# PAGE1.net
KiCad netlist of a schematic drawn in Altium Designer
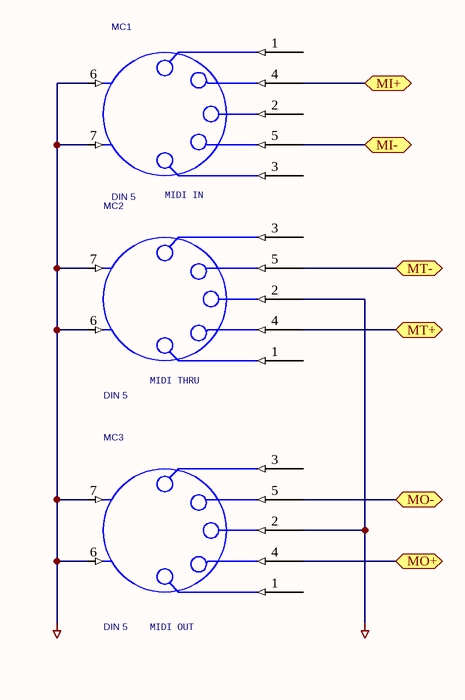
[diagram p0: PAGE1.SchDoc]

(export (version "E")
  (design (tool "Eeschema 10.0.6"))
  (components
    (comp (ref "MC1")
      (value "DIN 5")
      (fields (field (name "PART NO") "161-0505"))
      (libsource (lib "*") (part "DIN 5_0"))
    )
    (comp (ref "MC2")
      (value "DIN 5")
      (fields (field (name "PART NO") "161-0505"))
      (libsource (lib "*") (part "DIN 5_0"))
    )
    (comp (ref "MC3")
      (value "DIN 5")
      (fields (field (name "PART NO") "161-0505"))
      (libsource (lib "*") (part "DIN 5_0"))
    )
  )
  (nets
    (net (code "1") (name "/MI+") (class "Default")
      (node (ref "MC1") (pin "4") (pinfunction "4_4") (pintype "input"))
    )
    (net (code "2") (name "/MI-") (class "Default")
      (node (ref "MC1") (pin "5") (pinfunction "5_5") (pintype "input"))
    )
    (net (code "3") (name "/MO+") (class "Default")
      (node (ref "MC3") (pin "4") (pinfunction "4_4") (pintype "input"))
    )
    (net (code "4") (name "/MO-") (class "Default")
      (node (ref "MC3") (pin "5") (pinfunction "5_5") (pintype "input"))
    )
    (net (code "5") (name "/MT+") (class "Default")
      (node (ref "MC2") (pin "4") (pinfunction "4_4") (pintype "input"))
    )
    (net (code "6") (name "/MT-") (class "Default")
      (node (ref "MC2") (pin "5") (pinfunction "5_5") (pintype "input"))
    )
    (net (code "7") (name "AGND") (class "Default")
      (node (ref "MC1") (pin "6") (pinfunction "6_6") (pintype "input"))
      (node (ref "MC1") (pin "7") (pinfunction "7_7") (pintype "input"))
      (node (ref "MC2") (pin "2") (pinfunction "2_2") (pintype "input"))
      (node (ref "MC2") (pin "6") (pinfunction "6_6") (pintype "input"))
      (node (ref "MC2") (pin "7") (pinfunction "7_7") (pintype "input"))
      (node (ref "MC3") (pin "2") (pinfunction "2_2") (pintype "input"))
      (node (ref "MC3") (pin "6") (pinfunction "6_6") (pintype "input"))
      (node (ref "MC3") (pin "7") (pinfunction "7_7") (pintype "input"))
    )
    (net (code "8") (name "unconnected-(MC1-Pad1)") (class "Default")
      (node (ref "MC1") (pin "1") (pinfunction "1_1") (pintype "input"))
    )
    (net (code "9") (name "unconnected-(MC1-Pad2)") (class "Default")
      (node (ref "MC1") (pin "2") (pinfunction "2_2") (pintype "input"))
    )
    (net (code "10") (name "unconnected-(MC1-Pad3)") (class "Default")
      (node (ref "MC1") (pin "3") (pinfunction "3_3") (pintype "input"))
    )
    (net (code "11") (name "unconnected-(MC2-Pad1)") (class "Default")
      (node (ref "MC2") (pin "1") (pinfunction "1_1") (pintype "input"))
    )
    (net (code "12") (name "unconnected-(MC2-Pad3)") (class "Default")
      (node (ref "MC2") (pin "3") (pinfunction "3_3") (pintype "input"))
    )
    (net (code "13") (name "unconnected-(MC3-Pad1)") (class "Default")
      (node (ref "MC3") (pin "1") (pinfunction "1_1") (pintype "input"))
    )
    (net (code "14") (name "unconnected-(MC3-Pad3)") (class "Default")
      (node (ref "MC3") (pin "3") (pinfunction "3_3") (pintype "input"))
    )
  )
)
